# DIOT_Connectors.net
KiCad netlist of a schematic drawn in Altium Designer
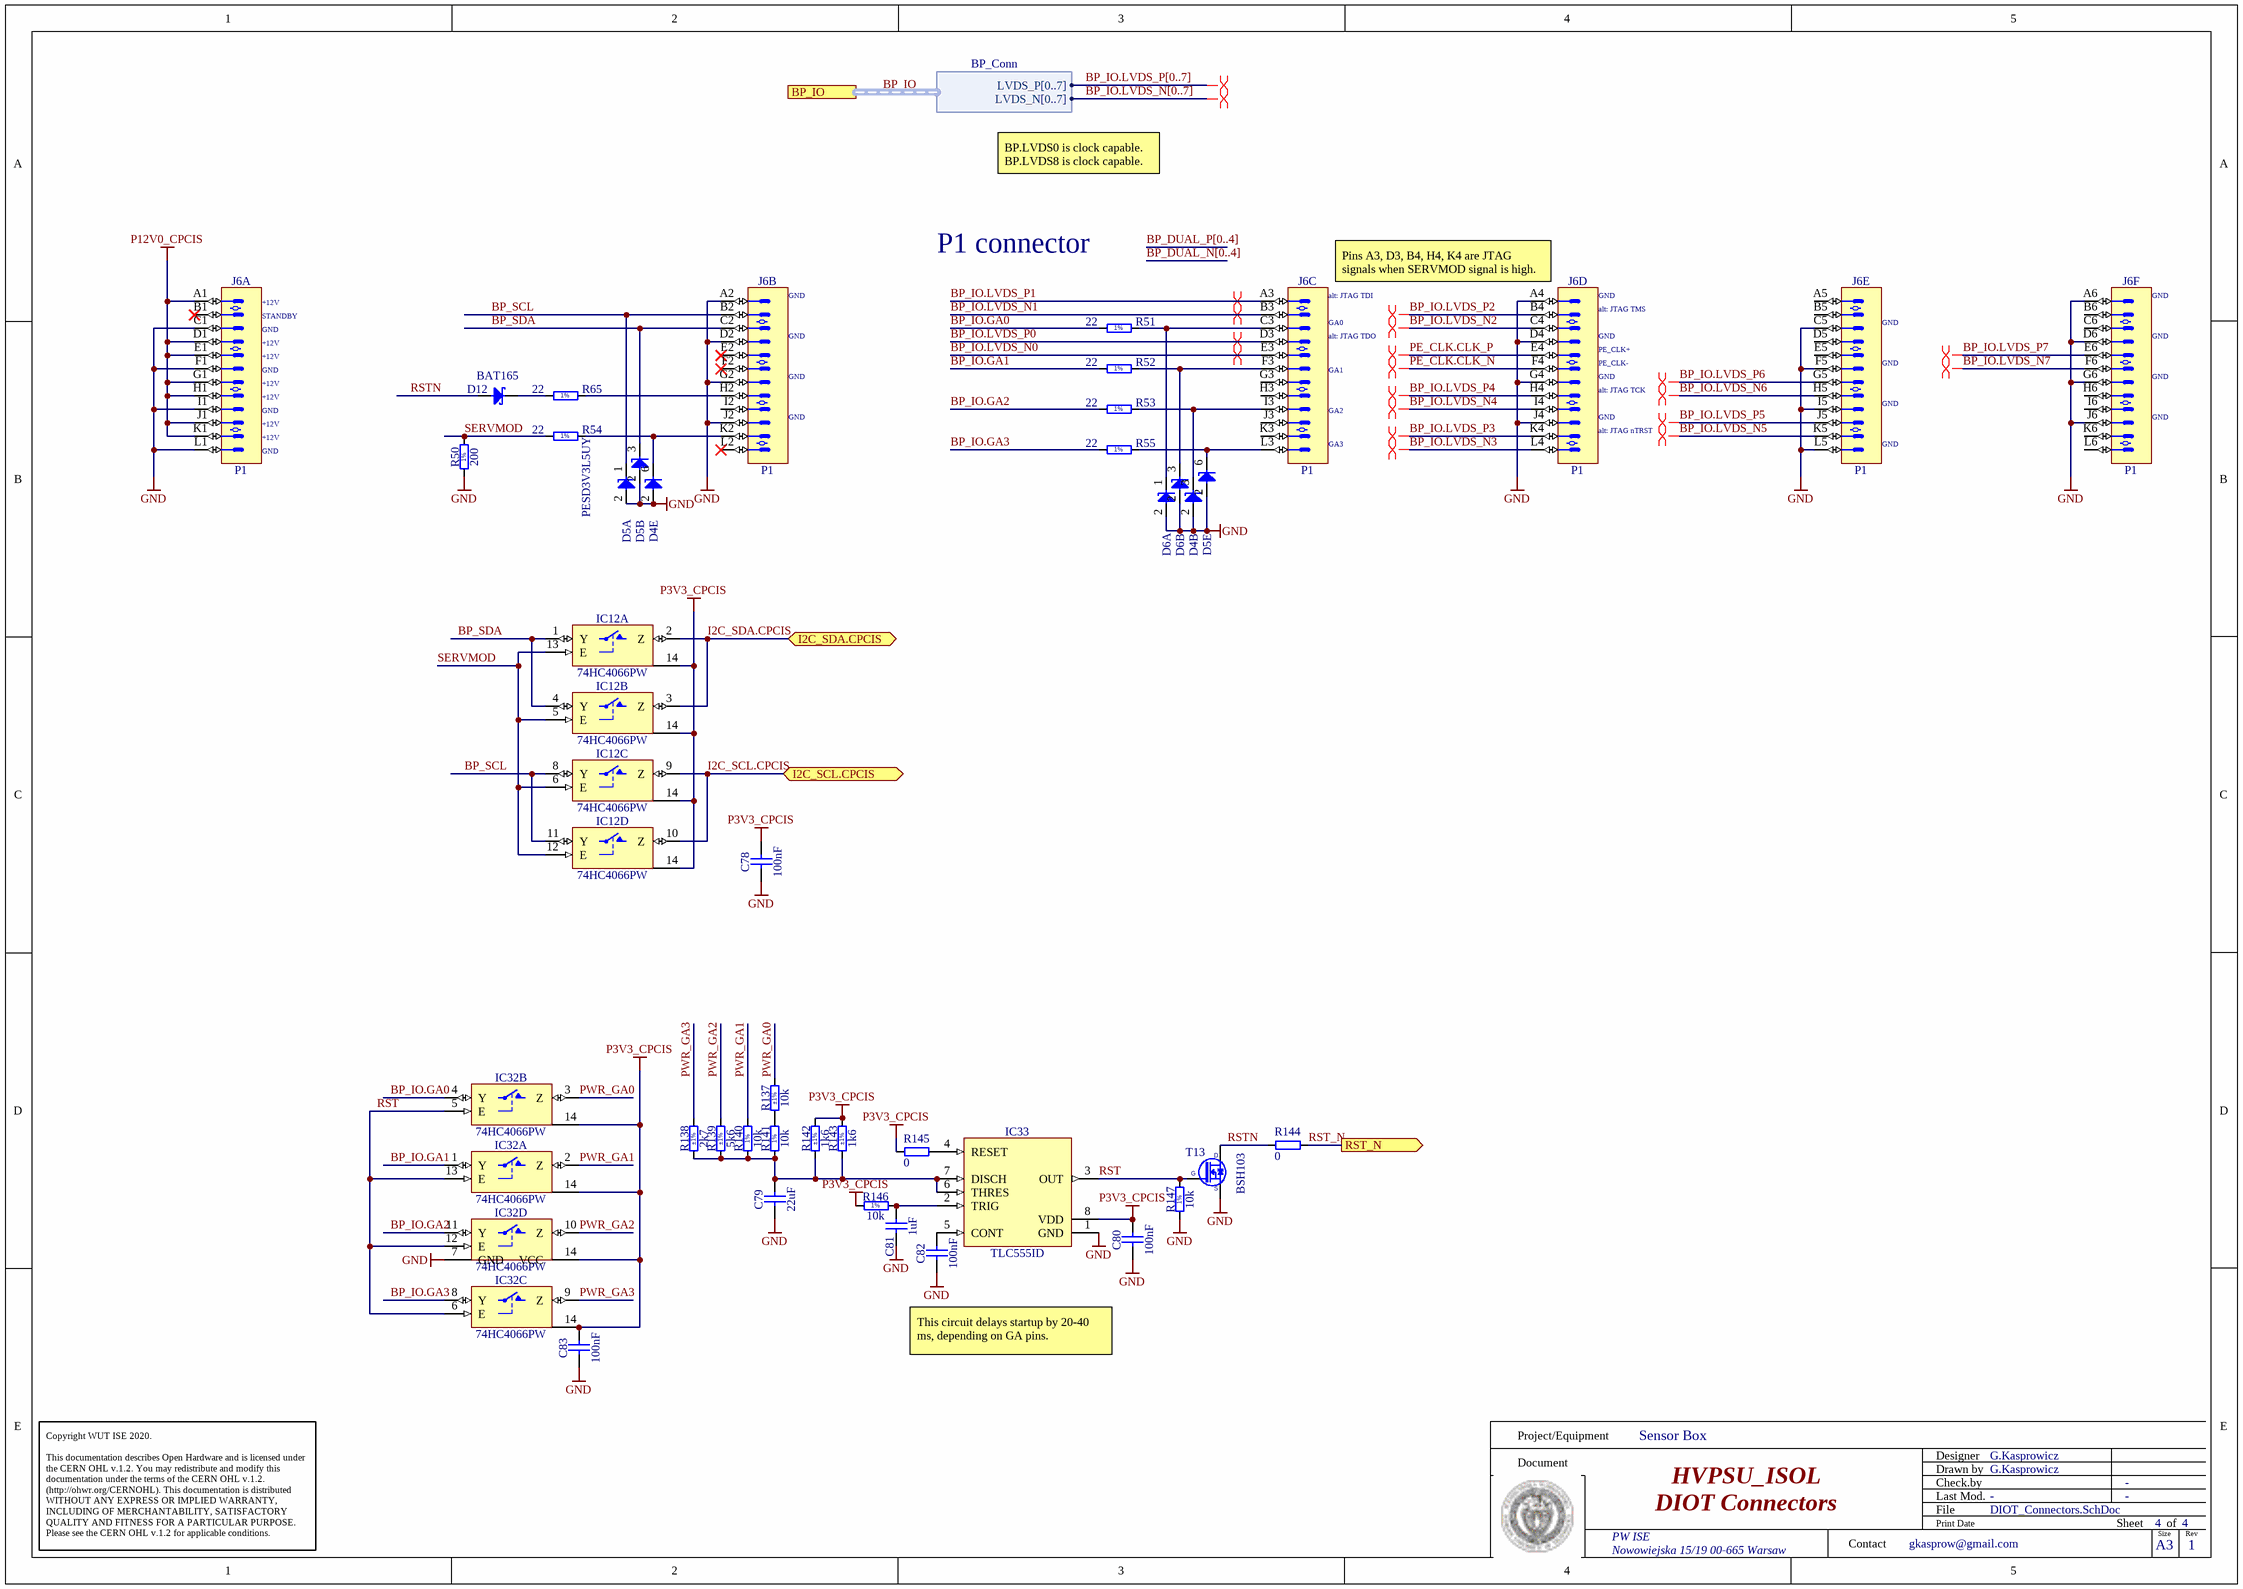
[diagram p0: DIOT_Connectors.SchDoc]

(export (version "E")
  (design (tool "Eeschema 10.0.6"))
  (components
    (comp (ref "C78")
      (value "100nF")
      (footprint "CAPC1005X55N")
      (description "Non-polarised capacitor")
      (fields
        (field (name "PART NUMBER") "CC0402_100NF_16V_10%_X5R")
        (field (name "VOLTAGE") "16V")
        (field (name "AUTHOR") "CERN DEM JLC")
      )
      (libsource (lib "Capacitors") (part "Capacitor - non polarized"))
    )
    (comp (ref "C79")
      (value "22uF")
      (footprint "CAPC1608X90N")
      (description "Non-polarised capacitor")
      (fields
        (field (name "MANUFACTURER") "GENERIC")
        (field (name "PART NUMBER") "CC0603_22UF_6.3V_20%_X5R")
        (field (name "AUTHOR") "CERN DEM JLC")
      )
      (libsource (lib "Capacitors") (part "Capacitor - non polarized"))
    )
    (comp (ref "C80")
      (value "100nF")
      (footprint "CAPC1005X55N")
      (description "Non-polarised capacitor")
      (fields
        (field (name "PART NUMBER") "CC0402_100NF_16V_10%_X5R")
        (field (name "VOLTAGE") "16V")
        (field (name "AUTHOR") "CERN DEM JLC")
      )
      (libsource (lib "Capacitors") (part "Capacitor - non polarized"))
    )
    (comp (ref "C81")
      (value "1uF")
      (footprint "CAPC1005X55N")
      (description "Non-polarised capacitor")
      (fields
        (field (name "PART NUMBER") "CC0402_1UF_16V_10%_X5R")
        (field (name "VOLTAGE") "16V")
        (field (name "AUTHOR") "CERN DEM JLC")
      )
      (libsource (lib "Capacitors") (part "Capacitor - non polarized"))
    )
    (comp (ref "C82")
      (value "100nF")
      (footprint "CAPC1005X55N")
      (description "Non-polarised capacitor")
      (fields
        (field (name "PART NUMBER") "CC0402_100NF_16V_10%_X5R")
        (field (name "VOLTAGE") "16V")
        (field (name "AUTHOR") "CERN DEM JLC")
      )
      (libsource (lib "Capacitors") (part "Capacitor - non polarized"))
    )
    (comp (ref "C83")
      (value "100nF")
      (footprint "CAPC1005X55N")
      (description "Non-polarised capacitor")
      (fields
        (field (name "PART NUMBER") "CC0402_100NF_16V_10%_X5R")
        (field (name "VOLTAGE") "16V")
        (field (name "AUTHOR") "CERN DEM JLC")
      )
      (libsource (lib "Capacitors") (part "Capacitor - non polarized"))
    )
    (comp (ref "D4")
      (value "PESD3V3L5UY")
      (footprint "SOT65P210X110-6N")
      (description "Fivefold ESD Protection Diode Arrays")
      (fields
        (field (name "VOLTAGE") "3.3V")
        (field (name "POWER") "200W")
        (field (name "AUTHOR") "CERN DEM WB")
      )
      (libsource (lib "ICs And Semiconductors") (part "PESD Array 5diodes 6pins Common anode2"))
    )
    (comp (ref "D5")
      (value "PESD3V3L5UY")
      (footprint "SOT65P210X110-6N")
      (description "Fivefold ESD Protection Diode Arrays")
      (fields
        (field (name "VOLTAGE") "3.3V")
        (field (name "POWER") "200W")
        (field (name "AUTHOR") "CERN DEM WB")
      )
      (libsource (lib "ICs And Semiconductors") (part "PESD Array 5diodes 6pins Common anode2"))
    )
    (comp (ref "D6")
      (value "PESD3V3L5UY")
      (footprint "SOT65P210X110-6N")
      (description "Fivefold ESD Protection Diode Arrays")
      (fields
        (field (name "VOLTAGE") "3.3V")
        (field (name "POWER") "200W")
        (field (name "AUTHOR") "CERN DEM WB")
      )
      (libsource (lib "ICs And Semiconductors") (part "PESD Array 5diodes 6pins Common anode2"))
    )
    (comp (ref "D12")
      (value "BAT165")
      (footprint "SOD2512X110N")
      (description "Schottky Diode")
      (fields
        (field (name "MANUFACTURER") "INFINEON")
        (field (name "VOLTAGE") "40V")
        (field (name "AUTHOR") "CERN DEM JLC")
      )
      (libsource (lib "ICs And Semiconductors") (part "Diode Schottky"))
    )
    (comp (ref "IC12")
      (value "74HC4066PW")
      (footprint "SOP65P640X110-14N")
      (fields (field (name "MANUFACTURER") "NXP SEMICONDUCTORS") (field (name "AUTHOR") "CERN DEM JLC"))
      (libsource (lib "ICs And Semiconductors") (part "4066"))
    )
    (comp (ref "IC32")
      (value "74HC4066PW")
      (footprint "SOP65P640X110-14N")
      (fields (field (name "MANUFACTURER") "NXP SEMICONDUCTORS") (field (name "AUTHOR") "CERN DEM JLC"))
      (libsource (lib "ICs And Semiconductors") (part "4066"))
    )
    (comp (ref "IC33")
      (value "TLC555ID")
      (footprint "SOIC127P600X175-8N")
      (description "LinCMOS Timer")
      (fields (field (name "MANUFACTURER") "TEXAS INSTRUMENTS") (field (name "AUTHOR") "CERN DEM JMW"))
      (libsource (lib "ICs And Semiconductors") (part "TLC555"))
    )
    (comp (ref "J6")
      (value "P1")
      (footprint "AMPHENOL_10052825-101LF")
      (description "72 Contacts Header, 6 Columns, 4 Pairs per Column")
      (fields
        (field (name "PART NUMBER") "AMPHENOL_10052825-101LF")
        (field (name "MANUFACTURER") "AMPHENOL")
        (field (name "AUTHOR") "CERN DEM MR")
      )
      (libsource (lib "Connectors") (part "AMPHENOL_10052825-101LF"))
    )
    (comp (ref "R50")
      (value "200")
      (footprint "RESC1005X40N")
      (description "Resistor - 1%")
      (fields
        (field (name "PART NUMBER") "R0402_200R_1%_0.0625W_100PPM")
        (field (name "POWER") "0.0625W")
        (field (name "AUTHOR") "CERN DEM JLC")
      )
      (libsource (lib "Resistors") (part "Resistor - 1%"))
    )
    (comp (ref "R51")
      (value "22")
      (footprint "RESC1005X40N")
      (description "Resistor - 1%")
      (fields
        (field (name "PART NUMBER") "R0402_22R_1%_0.0625W_100PPM")
        (field (name "POWER") "0.0625W")
        (field (name "AUTHOR") "CERN DEM JLC")
      )
      (libsource (lib "Resistors") (part "Resistor - 1%"))
    )
    (comp (ref "R52")
      (value "22")
      (footprint "RESC1005X40N")
      (description "Resistor - 1%")
      (fields
        (field (name "PART NUMBER") "R0402_22R_1%_0.0625W_100PPM")
        (field (name "POWER") "0.0625W")
        (field (name "AUTHOR") "CERN DEM JLC")
      )
      (libsource (lib "Resistors") (part "Resistor - 1%"))
    )
    (comp (ref "R53")
      (value "22")
      (footprint "RESC1005X40N")
      (description "Resistor - 1%")
      (fields
        (field (name "PART NUMBER") "R0402_22R_1%_0.0625W_100PPM")
        (field (name "POWER") "0.0625W")
        (field (name "AUTHOR") "CERN DEM JLC")
      )
      (libsource (lib "Resistors") (part "Resistor - 1%"))
    )
    (comp (ref "R54")
      (value "22")
      (footprint "RESC1005X40N")
      (description "Resistor - 1%")
      (fields
        (field (name "PART NUMBER") "R0402_22R_1%_0.0625W_100PPM")
        (field (name "POWER") "0.0625W")
        (field (name "AUTHOR") "CERN DEM JLC")
      )
      (libsource (lib "Resistors") (part "Resistor - 1%"))
    )
    (comp (ref "R55")
      (value "22")
      (footprint "RESC1005X40N")
      (description "Resistor - 1%")
      (fields
        (field (name "PART NUMBER") "R0402_22R_1%_0.0625W_100PPM")
        (field (name "POWER") "0.0625W")
        (field (name "AUTHOR") "CERN DEM JLC")
      )
      (libsource (lib "Resistors") (part "Resistor - 1%"))
    )
    (comp (ref "R65")
      (value "22")
      (footprint "RESC1005X40N")
      (description "Resistor - 1%")
      (fields
        (field (name "PART NUMBER") "R0402_22R_1%_0.0625W_100PPM")
        (field (name "POWER") "0.0625W")
        (field (name "AUTHOR") "CERN DEM JLC")
      )
      (libsource (lib "Resistors") (part "Resistor - 1%"))
    )
    (comp (ref "R137")
      (value "10k")
      (footprint "RESC1005X40N")
      (description "Resistor - 1%")
      (fields
        (field (name "PART NUMBER") "R0402_10K_1%_0.0625W_100PPM")
        (field (name "POWER") "0.0625W")
        (field (name "TOLERANCE") "±1%")
        (field (name "AUTHOR") "CERN DEM JLC")
      )
      (libsource (lib "Resistors") (part "Resistor - 1%"))
    )
    (comp (ref "R138")
      (value "2k7")
      (footprint "RESC1608X55N")
      (description "Resistor - 1%")
      (fields
        (field (name "PART NUMBER") "R0603_2K7_1%_0.1W_100PPM")
        (field (name "POWER") "0.1W")
        (field (name "TOLERANCE") "±1%")
        (field (name "AUTHOR") "CERN DEM JLC")
      )
      (libsource (lib "") (part "Resistor - 1%_1"))
    )
    (comp (ref "R139")
      (value "5k6")
      (footprint "RESC1005X40N")
      (description "Resistor - 1%")
      (fields
        (field (name "PART NUMBER") "R0402_5K6_1%_0.0625W_100PPM")
        (field (name "POWER") "0.0625W")
        (field (name "TOLERANCE") "±1%")
        (field (name "AUTHOR") "CERN DEM JLC")
      )
      (libsource (lib "Resistors") (part "Resistor - 1%"))
    )
    (comp (ref "R140")
      (value "10k")
      (footprint "RESC1005X40N")
      (description "Resistor - 1%")
      (fields
        (field (name "PART NUMBER") "R0402_1K_1%_0.0625W_100PPM")
        (field (name "POWER") "0.0625W")
        (field (name "AUTHOR") "CERN DEM JLC")
      )
      (libsource (lib "Resistors") (part "Resistor - 1%"))
    )
    (comp (ref "R141")
      (value "10k")
      (footprint "RESC1005X40N")
      (description "Resistor - 1%")
      (fields
        (field (name "PART NUMBER") "R0402_1K_1%_0.0625W_100PPM")
        (field (name "POWER") "0.0625W")
        (field (name "AUTHOR") "CERN DEM JLC")
      )
      (libsource (lib "Resistors") (part "Resistor - 1%"))
    )
    (comp (ref "R142")
      (value "1k6")
      (footprint "RESC1005X40N")
      (description "Resistor - 1%")
      (fields
        (field (name "PART NUMBER") "R0402_1K6_1%_0.0625W_100PPM")
        (field (name "POWER") "0.0625W")
        (field (name "TOLERANCE") "±1%")
        (field (name "AUTHOR") "CERN DEM JLC")
      )
      (libsource (lib "Resistors") (part "Resistor - 1%"))
    )
    (comp (ref "R143")
      (value "1k6")
      (footprint "RESC1005X40N")
      (description "Resistor - 1%")
      (fields
        (field (name "PART NUMBER") "R0402_1K6_1%_0.0625W_100PPM")
        (field (name "POWER") "0.0625W")
        (field (name "TOLERANCE") "±1%")
        (field (name "AUTHOR") "CERN DEM JLC")
      )
      (libsource (lib "Resistors") (part "Resistor - 1%"))
    )
    (comp (ref "R144")
      (value "0")
      (footprint "RESC1005X40N")
      (description "Resistor")
      (fields
        (field (name "PART NUMBER") "R0402_0R_JUMPER")
        (field (name "MANUFACTURER") "GENERIC")
        (field (name "AUTHOR") "CERN DEM JLC")
      )
      (libsource (lib "Resistors") (part "Resistor"))
    )
    (comp (ref "R145")
      (value "0")
      (footprint "RESC1005X40N")
      (description "Resistor")
      (fields
        (field (name "PART NUMBER") "R0402_0R_JUMPER")
        (field (name "MANUFACTURER") "GENERIC")
        (field (name "AUTHOR") "CERN DEM JLC")
      )
      (libsource (lib "Resistors") (part "Resistor"))
    )
    (comp (ref "R146")
      (value "10k")
      (footprint "RESC1005X40N")
      (description "Resistor - 1%")
      (fields
        (field (name "PART NUMBER") "R0402_10K_1%_0.0625W_100PPM")
        (field (name "POWER") "0.0625W")
        (field (name "AUTHOR") "CERN DEM JLC")
      )
      (libsource (lib "Resistors") (part "Resistor - 1%"))
    )
    (comp (ref "R147")
      (value "10k")
      (footprint "RESC1005X40N")
      (description "Resistor - 1%")
      (fields
        (field (name "PART NUMBER") "R0402_10K_1%_0.0625W_100PPM")
        (field (name "POWER") "0.0625W")
        (field (name "AUTHOR") "CERN DEM JLC")
      )
      (libsource (lib "Resistors") (part "Resistor - 1%"))
    )
    (comp (ref "T13")
      (value "BSH103")
      (footprint "SOT95P230X110-3N")
      (description "N-CHANNEL MOSFET WITH DIODE")
      (fields (field (name "MANUFACTURER") "NEXPERIA") (field (name "AUTHOR") "CERN DEM JLC"))
      (libsource (lib "ICs And Semiconductors") (part "N-MOSFET-D 1G 2S 3D"))
    )
  )
  (nets
    (net (code "14") (name "/BP_IO.GA0") (class "Default")
      (node (ref "IC32") (pin "4") (pinfunction "Y_4") (pintype "bidirectional"))
      (node (ref "R51") (pin "1") (pinfunction "1_1") (pintype "passive"))
    )
    (net (code "15") (name "/BP_IO.GA1") (class "Default")
      (node (ref "IC32") (pin "1") (pinfunction "Y_1") (pintype "bidirectional"))
      (node (ref "R52") (pin "1") (pinfunction "1_1") (pintype "passive"))
    )
    (net (code "16") (name "/BP_IO.GA2") (class "Default")
      (node (ref "IC32") (pin "11") (pinfunction "Y_11") (pintype "bidirectional"))
      (node (ref "R53") (pin "1") (pinfunction "1_1") (pintype "passive"))
    )
    (net (code "17") (name "/BP_IO.GA3") (class "Default")
      (node (ref "IC32") (pin "8") (pinfunction "Y_8") (pintype "bidirectional"))
      (node (ref "R55") (pin "1") (pinfunction "1_1") (pintype "passive"))
    )
    (net (code "18") (name "/BP_IO.LVDS_N0") (class "Default")
      (node (ref "J6") (pin "E3") (pinfunction "E3_E3") (pintype "bidirectional"))
    )
    (net (code "19") (name "/BP_IO.LVDS_N1") (class "Default")
      (node (ref "J6") (pin "B3") (pinfunction "B3_B3") (pintype "bidirectional"))
    )
    (net (code "20") (name "/BP_IO.LVDS_N2") (class "Default")
      (node (ref "J6") (pin "C4") (pinfunction "C4_C4") (pintype "bidirectional"))
    )
    (net (code "21") (name "/BP_IO.LVDS_N3") (class "Default")
      (node (ref "J6") (pin "L4") (pinfunction "L4_L4") (pintype "bidirectional"))
    )
    (net (code "22") (name "/BP_IO.LVDS_N4") (class "Default")
      (node (ref "J6") (pin "I4") (pinfunction "I4_I4") (pintype "bidirectional"))
    )
    (net (code "23") (name "/BP_IO.LVDS_N5") (class "Default")
      (node (ref "J6") (pin "K5") (pinfunction "K5_K5") (pintype "bidirectional"))
    )
    (net (code "24") (name "/BP_IO.LVDS_N6") (class "Default")
      (node (ref "J6") (pin "H5") (pinfunction "H5_H5") (pintype "bidirectional"))
    )
    (net (code "25") (name "/BP_IO.LVDS_N7") (class "Default")
      (node (ref "J6") (pin "F6") (pinfunction "F6_F6") (pintype "bidirectional"))
    )
    (net (code "27") (name "/BP_IO.LVDS_P0") (class "Default")
      (node (ref "J6") (pin "D3") (pinfunction "D3_D3") (pintype "bidirectional"))
    )
    (net (code "28") (name "/BP_IO.LVDS_P1") (class "Default")
      (node (ref "J6") (pin "A3") (pinfunction "A3_A3") (pintype "bidirectional"))
    )
    (net (code "29") (name "/BP_IO.LVDS_P2") (class "Default")
      (node (ref "J6") (pin "B4") (pinfunction "B4_B4") (pintype "bidirectional"))
    )
    (net (code "30") (name "/BP_IO.LVDS_P3") (class "Default")
      (node (ref "J6") (pin "K4") (pinfunction "K4_K4") (pintype "bidirectional"))
    )
    (net (code "31") (name "/BP_IO.LVDS_P4") (class "Default")
      (node (ref "J6") (pin "H4") (pinfunction "H4_H4") (pintype "bidirectional"))
    )
    (net (code "32") (name "/BP_IO.LVDS_P5") (class "Default")
      (node (ref "J6") (pin "J5") (pinfunction "J5_J5") (pintype "bidirectional"))
    )
    (net (code "33") (name "/BP_IO.LVDS_P6") (class "Default")
      (node (ref "J6") (pin "G5") (pinfunction "G5_G5") (pintype "bidirectional"))
    )
    (net (code "34") (name "/BP_IO.LVDS_P7") (class "Default")
      (node (ref "J6") (pin "E6") (pinfunction "E6_E6") (pintype "bidirectional"))
    )
    (net (code "35") (name "/BP_SCL") (class "Default")
      (node (ref "D5") (pin "1") (pinfunction "C_1") (pintype "passive"))
      (node (ref "IC12") (pin "11") (pinfunction "Y_11") (pintype "bidirectional"))
      (node (ref "IC12") (pin "8") (pinfunction "Y_8") (pintype "bidirectional"))
      (node (ref "J6") (pin "B2") (pinfunction "B2_B2") (pintype "bidirectional"))
    )
    (net (code "36") (name "/BP_SDA") (class "Default")
      (node (ref "D5") (pin "3") (pinfunction "C_3") (pintype "passive"))
      (node (ref "IC12") (pin "1") (pinfunction "Y_1") (pintype "bidirectional"))
      (node (ref "IC12") (pin "4") (pinfunction "Y_4") (pintype "bidirectional"))
      (node (ref "J6") (pin "C2") (pinfunction "C2_C2") (pintype "bidirectional"))
    )
    (net (code "37") (name "/I2C_SCL.CPCIS") (class "Default")
      (node (ref "IC12") (pin "10") (pinfunction "Z_10") (pintype "bidirectional"))
      (node (ref "IC12") (pin "9") (pinfunction "Z_9") (pintype "bidirectional"))
    )
    (net (code "38") (name "/I2C_SDA.CPCIS") (class "Default")
      (node (ref "IC12") (pin "2") (pinfunction "Z_2") (pintype "bidirectional"))
      (node (ref "IC12") (pin "3") (pinfunction "Z_3") (pintype "bidirectional"))
    )
    (net (code "39") (name "/PE_CLK.CLK_N") (class "Default")
      (node (ref "J6") (pin "F4") (pinfunction "F4_F4") (pintype "bidirectional"))
    )
    (net (code "40") (name "/PE_CLK.CLK_P") (class "Default")
      (node (ref "J6") (pin "E4") (pinfunction "E4_E4") (pintype "bidirectional"))
    )
    (net (code "41") (name "/PWR_GA0") (class "Default")
      (node (ref "IC32") (pin "3") (pinfunction "Z_3") (pintype "bidirectional"))
      (node (ref "R137") (pin "2") (pinfunction "2_2") (pintype "passive"))
    )
    (net (code "42") (name "/PWR_GA1") (class "Default")
      (node (ref "IC32") (pin "2") (pinfunction "Z_2") (pintype "bidirectional"))
      (node (ref "R140") (pin "2") (pinfunction "2_2") (pintype "passive"))
    )
    (net (code "43") (name "/PWR_GA2") (class "Default")
      (node (ref "IC32") (pin "10") (pinfunction "Z_10") (pintype "bidirectional"))
      (node (ref "R139") (pin "2") (pinfunction "2_2") (pintype "passive"))
    )
    (net (code "44") (name "/PWR_GA3") (class "Default")
      (node (ref "IC32") (pin "9") (pinfunction "Z_9") (pintype "bidirectional"))
      (node (ref "R138") (pin "2") (pinfunction "2_2") (pintype "passive"))
    )
    (net (code "45") (name "/RST") (class "Default")
      (node (ref "IC32") (pin "12") (pinfunction "E_12") (pintype "input"))
      (node (ref "IC32") (pin "13") (pinfunction "E_13") (pintype "input"))
      (node (ref "IC32") (pin "5") (pinfunction "E_5") (pintype "input"))
      (node (ref "IC32") (pin "6") (pinfunction "E_6") (pintype "input"))
      (node (ref "IC33") (pin "3") (pinfunction "OUT_3") (pintype "output"))
      (node (ref "R147") (pin "2") (pinfunction "2_2") (pintype "passive"))
      (node (ref "T13") (pin "1") (pinfunction "G_1") (pintype "passive"))
    )
    (net (code "46") (name "/RSTN") (class "Default")
      (node (ref "D12") (pin "2") (pinfunction "A_2") (pintype "passive"))
      (node (ref "R144") (pin "2") (pinfunction "2_2") (pintype "passive"))
      (node (ref "T13") (pin "3") (pinfunction "D_3") (pintype "passive"))
    )
    (net (code "47") (name "/RST_N") (class "Default")
      (node (ref "R144") (pin "1") (pinfunction "1_1") (pintype "passive"))
    )
    (net (code "48") (name "/SERVMOD") (class "Default")
      (node (ref "IC12") (pin "12") (pinfunction "E_12") (pintype "input"))
      (node (ref "IC12") (pin "13") (pinfunction "E_13") (pintype "input"))
      (node (ref "IC12") (pin "5") (pinfunction "E_5") (pintype "input"))
      (node (ref "IC12") (pin "6") (pinfunction "E_6") (pintype "input"))
      (node (ref "R50") (pin "2") (pinfunction "2_2") (pintype "passive"))
      (node (ref "R54") (pin "1") (pinfunction "1_1") (pintype "passive"))
    )
    (net (code "51") (name "GND") (class "Default")
      (node (ref "C78") (pin "1") (pinfunction "1_1") (pintype "passive"))
      (node (ref "C79") (pin "1") (pinfunction "1_1") (pintype "passive"))
      (node (ref "C80") (pin "1") (pinfunction "1_1") (pintype "passive"))
      (node (ref "C81") (pin "1") (pinfunction "1_1") (pintype "passive"))
      (node (ref "C82") (pin "1") (pinfunction "1_1") (pintype "passive"))
      (node (ref "C83") (pin "1") (pinfunction "1_1") (pintype "passive"))
      (node (ref "D4") (pin "2") (pinfunction "A_2") (pintype "passive"))
      (node (ref "D5") (pin "2") (pinfunction "A_2") (pintype "passive"))
      (node (ref "D6") (pin "2") (pinfunction "A_2") (pintype "passive"))
      (node (ref "IC12") (pin "7") (pinfunction "GND_7") (pintype "power_in"))
      (node (ref "IC32") (pin "7") (pinfunction "GND_7") (pintype "power_in"))
      (node (ref "IC33") (pin "1") (pinfunction "GND_1") (pintype "power_in"))
      (node (ref "J6") (pin "A2") (pinfunction "A2_A2") (pintype "bidirectional"))
      (node (ref "J6") (pin "A4") (pinfunction "A4_A4") (pintype "bidirectional"))
      (node (ref "J6") (pin "A6") (pinfunction "A6_A6") (pintype "bidirectional"))
      (node (ref "J6") (pin "C1") (pinfunction "C1_C1") (pintype "bidirectional"))
      (node (ref "J6") (pin "C5") (pinfunction "C5_C5") (pintype "bidirectional"))
      (node (ref "J6") (pin "D2") (pinfunction "D2_D2") (pintype "bidirectional"))
      (node (ref "J6") (pin "D4") (pinfunction "D4_D4") (pintype "bidirectional"))
      (node (ref "J6") (pin "D6") (pinfunction "D6_D6") (pintype "bidirectional"))
      (node (ref "J6") (pin "F1") (pinfunction "F1_F1") (pintype "bidirectional"))
      (node (ref "J6") (pin "F5") (pinfunction "F5_F5") (pintype "bidirectional"))
      (node (ref "J6") (pin "G2") (pinfunction "G2_G2") (pintype "bidirectional"))
      (node (ref "J6") (pin "G4") (pinfunction "G4_G4") (pintype "bidirectional"))
      (node (ref "J6") (pin "G6") (pinfunction "G6_G6") (pintype "bidirectional"))
      (node (ref "J6") (pin "I1") (pinfunction "I1_I1") (pintype "bidirectional"))
      (node (ref "J6") (pin "I5") (pinfunction "I5_I5") (pintype "bidirectional"))
      (node (ref "J6") (pin "J2") (pinfunction "J2_J2") (pintype "bidirectional"))
      (node (ref "J6") (pin "J4") (pinfunction "J4_J4") (pintype "bidirectional"))
      (node (ref "J6") (pin "J6") (pinfunction "J6_J6") (pintype "bidirectional"))
      (node (ref "J6") (pin "L1") (pinfunction "L1_L1") (pintype "bidirectional"))
      (node (ref "J6") (pin "L5") (pinfunction "L5_L5") (pintype "bidirectional"))
      (node (ref "R147") (pin "1") (pinfunction "1_1") (pintype "passive"))
      (node (ref "R50") (pin "1") (pinfunction "1_1") (pintype "passive"))
      (node (ref "T13") (pin "2") (pinfunction "S_2") (pintype "passive"))
    )
    (net (code "52") (name "Net-(D4B-C)") (class "Default")
      (node (ref "D4") (pin "3") (pinfunction "C_3") (pintype "passive"))
      (node (ref "J6") (pin "I3") (pinfunction "I3_I3") (pintype "bidirectional"))
      (node (ref "R53") (pin "2") (pinfunction "2_2") (pintype "passive"))
    )
    (net (code "53") (name "Net-(D4E-C)") (class "Default")
      (node (ref "D4") (pin "6") (pinfunction "C_6") (pintype "passive"))
      (node (ref "J6") (pin "K2") (pinfunction "K2_K2") (pintype "bidirectional"))
      (node (ref "R54") (pin "2") (pinfunction "2_2") (pintype "passive"))
    )
    (net (code "54") (name "Net-(D5E-C)") (class "Default")
      (node (ref "D5") (pin "6") (pinfunction "C_6") (pintype "passive"))
      (node (ref "J6") (pin "L3") (pinfunction "L3_L3") (pintype "bidirectional"))
      (node (ref "R55") (pin "2") (pinfunction "2_2") (pintype "passive"))
    )
    (net (code "55") (name "Net-(D6A-C)") (class "Default")
      (node (ref "D6") (pin "1") (pinfunction "C_1") (pintype "passive"))
      (node (ref "J6") (pin "C3") (pinfunction "C3_C3") (pintype "bidirectional"))
      (node (ref "R51") (pin "2") (pinfunction "2_2") (pintype "passive"))
    )
    (net (code "56") (name "Net-(D6B-C)") (class "Default")
      (node (ref "D6") (pin "3") (pinfunction "C_3") (pintype "passive"))
      (node (ref "J6") (pin "F3") (pinfunction "F3_F3") (pintype "bidirectional"))
      (node (ref "R52") (pin "2") (pinfunction "2_2") (pintype "passive"))
    )
    (net (code "57") (name "Net-(D12-C)") (class "Default")
      (node (ref "D12") (pin "1") (pinfunction "C_1") (pintype "passive"))
      (node (ref "R65") (pin "1") (pinfunction "1_1") (pintype "passive"))
    )
    (net (code "58") (name "Net-(IC33-CONT)") (class "Default")
      (node (ref "C82") (pin "2") (pinfunction "2_2") (pintype "passive"))
      (node (ref "IC33") (pin "5") (pinfunction "CONT_5") (pintype "input"))
    )
    (net (code "59") (name "Net-(IC33-DISCH)") (class "Default")
      (node (ref "C79") (pin "2") (pinfunction "2_2") (pintype "passive"))
      (node (ref "IC33") (pin "6") (pinfunction "THRES_6") (pintype "input"))
      (node (ref "IC33") (pin "7") (pinfunction "DISCH_7") (pintype "input"))
      (node (ref "R138") (pin "1") (pinfunction "1_1") (pintype "passive"))
      (node (ref "R139") (pin "1") (pinfunction "1_1") (pintype "passive"))
      (node (ref "R140") (pin "1") (pinfunction "1_1") (pintype "passive"))
      (node (ref "R141") (pin "1") (pinfunction "1_1") (pintype "passive"))
      (node (ref "R142") (pin "1") (pinfunction "1_1") (pintype "passive"))
      (node (ref "R143") (pin "1") (pinfunction "1_1") (pintype "passive"))
    )
    (net (code "60") (name "Net-(IC33-RESET)") (class "Default")
      (node (ref "IC33") (pin "4") (pinfunction "RESET_4") (pintype "input"))
      (node (ref "R145") (pin "1") (pinfunction "1_1") (pintype "passive"))
    )
    (net (code "61") (name "Net-(IC33-TRIG)") (class "Default")
      (node (ref "C81") (pin "2") (pinfunction "2_2") (pintype "passive"))
      (node (ref "IC33") (pin "2") (pinfunction "TRIG_2") (pintype "input"))
      (node (ref "R146") (pin "2") (pinfunction "2_2") (pintype "passive"))
    )
    (net (code "62") (name "Net-(J6-PadH2)") (class "Default")
      (node (ref "J6") (pin "H2") (pinfunction "H2_H2") (pintype "bidirectional"))
      (node (ref "R65") (pin "2") (pinfunction "2_2") (pintype "passive"))
    )
    (net (code "63") (name "Net-(R137-Pad1)") (class "Default")
      (node (ref "R137") (pin "1") (pinfunction "1_1") (pintype "passive"))
      (node (ref "R141") (pin "2") (pinfunction "2_2") (pintype "passive"))
    )
    (net (code "64") (name "P3V3_CPCIS") (class "Default")
      (node (ref "C78") (pin "2") (pinfunction "2_2") (pintype "passive"))
      (node (ref "C80") (pin "2") (pinfunction "2_2") (pintype "passive"))
      (node (ref "C83") (pin "2") (pinfunction "2_2") (pintype "passive"))
      (node (ref "IC12") (pin "14") (pinfunction "VCC_14") (pintype "power_in"))
      (node (ref "IC32") (pin "14") (pinfunction "VCC_14") (pintype "power_in"))
      (node (ref "IC33") (pin "8") (pinfunction "VDD_8") (pintype "power_in"))
      (node (ref "R142") (pin "2") (pinfunction "2_2") (pintype "passive"))
      (node (ref "R143") (pin "2") (pinfunction "2_2") (pintype "passive"))
      (node (ref "R145") (pin "2") (pinfunction "2_2") (pintype "passive"))
      (node (ref "R146") (pin "1") (pinfunction "1_1") (pintype "passive"))
    )
    (net (code "65") (name "P12V0_CPCIS") (class "Default")
      (node (ref "J6") (pin "A1") (pinfunction "A1_A1") (pintype "bidirectional"))
      (node (ref "J6") (pin "D1") (pinfunction "D1_D1") (pintype "bidirectional"))
      (node (ref "J6") (pin "E1") (pinfunction "E1_E1") (pintype "bidirectional"))
      (node (ref "J6") (pin "G1") (pinfunction "G1_G1") (pintype "bidirectional"))
      (node (ref "J6") (pin "H1") (pinfunction "H1_H1") (pintype "bidirectional"))
      (node (ref "J6") (pin "J1") (pinfunction "J1_J1") (pintype "bidirectional"))
      (node (ref "J6") (pin "K1") (pinfunction "K1_K1") (pintype "bidirectional"))
    )
    (net (code "66") (name "unconnected-(J6-PadA5)") (class "Default")
      (node (ref "J6") (pin "A5") (pinfunction "A5_A5") (pintype "bidirectional"))
    )
    (net (code "67") (name "unconnected-(J6-PadB1)") (class "Default")
      (node (ref "J6") (pin "B1") (pinfunction "B1_B1") (pintype "bidirectional+no_connect"))
    )
    (net (code "68") (name "unconnected-(J6-PadB5)") (class "Default")
      (node (ref "J6") (pin "B5") (pinfunction "B5_B5") (pintype "bidirectional"))
    )
    (net (code "69") (name "unconnected-(J6-PadB6)") (class "Default")
      (node (ref "J6") (pin "B6") (pinfunction "B6_B6") (pintype "bidirectional"))
    )
    (net (code "70") (name "unconnected-(J6-PadC6)") (class "Default")
      (node (ref "J6") (pin "C6") (pinfunction "C6_C6") (pintype "bidirectional"))
    )
    (net (code "71") (name "unconnected-(J6-PadD5)") (class "Default")
      (node (ref "J6") (pin "D5") (pinfunction "D5_D5") (pintype "bidirectional"))
    )
    (net (code "72") (name "unconnected-(J6-PadE2)") (class "Default")
      (node (ref "J6") (pin "E2") (pinfunction "E2_E2") (pintype "bidirectional+no_connect"))
    )
    (net (code "73") (name "unconnected-(J6-PadE5)") (class "Default")
      (node (ref "J6") (pin "E5") (pinfunction "E5_E5") (pintype "bidirectional"))
    )
    (net (code "74") (name "unconnected-(J6-PadF2)") (class "Default")
      (node (ref "J6") (pin "F2") (pinfunction "F2_F2") (pintype "bidirectional+no_connect"))
    )
    (net (code "75") (name "unconnected-(J6-PadG3)") (class "Default")
      (node (ref "J6") (pin "G3") (pinfunction "G3_G3") (pintype "bidirectional"))
    )
    (net (code "76") (name "unconnected-(J6-PadH3)") (class "Default")
      (node (ref "J6") (pin "H3") (pinfunction "H3_H3") (pintype "bidirectional"))
    )
    (net (code "77") (name "unconnected-(J6-PadH6)") (class "Default")
      (node (ref "J6") (pin "H6") (pinfunction "H6_H6") (pintype "bidirectional"))
    )
    (net (code "78") (name "unconnected-(J6-PadI2)") (class "Default")
      (node (ref "J6") (pin "I2") (pinfunction "I2_I2") (pintype "bidirectional"))
    )
    (net (code "79") (name "unconnected-(J6-PadI6)") (class "Default")
      (node (ref "J6") (pin "I6") (pinfunction "I6_I6") (pintype "bidirectional"))
    )
    (net (code "80") (name "unconnected-(J6-PadJ3)") (class "Default")
      (node (ref "J6") (pin "J3") (pinfunction "J3_J3") (pintype "bidirectional"))
    )
    (net (code "81") (name "unconnected-(J6-PadK3)") (class "Default")
      (node (ref "J6") (pin "K3") (pinfunction "K3_K3") (pintype "bidirectional"))
    )
    (net (code "82") (name "unconnected-(J6-PadK6)") (class "Default")
      (node (ref "J6") (pin "K6") (pinfunction "K6_K6") (pintype "bidirectional"))
    )
    (net (code "83") (name "unconnected-(J6-PadL2)") (class "Default")
      (node (ref "J6") (pin "L2") (pinfunction "L2_L2") (pintype "bidirectional+no_connect"))
    )
    (net (code "84") (name "unconnected-(J6-PadL6)") (class "Default")
      (node (ref "J6") (pin "L6") (pinfunction "L6_L6") (pintype "bidirectional"))
    )
  )
)
